# PicoBoard.net
KiCad netlist of a schematic drawn in EAGLE
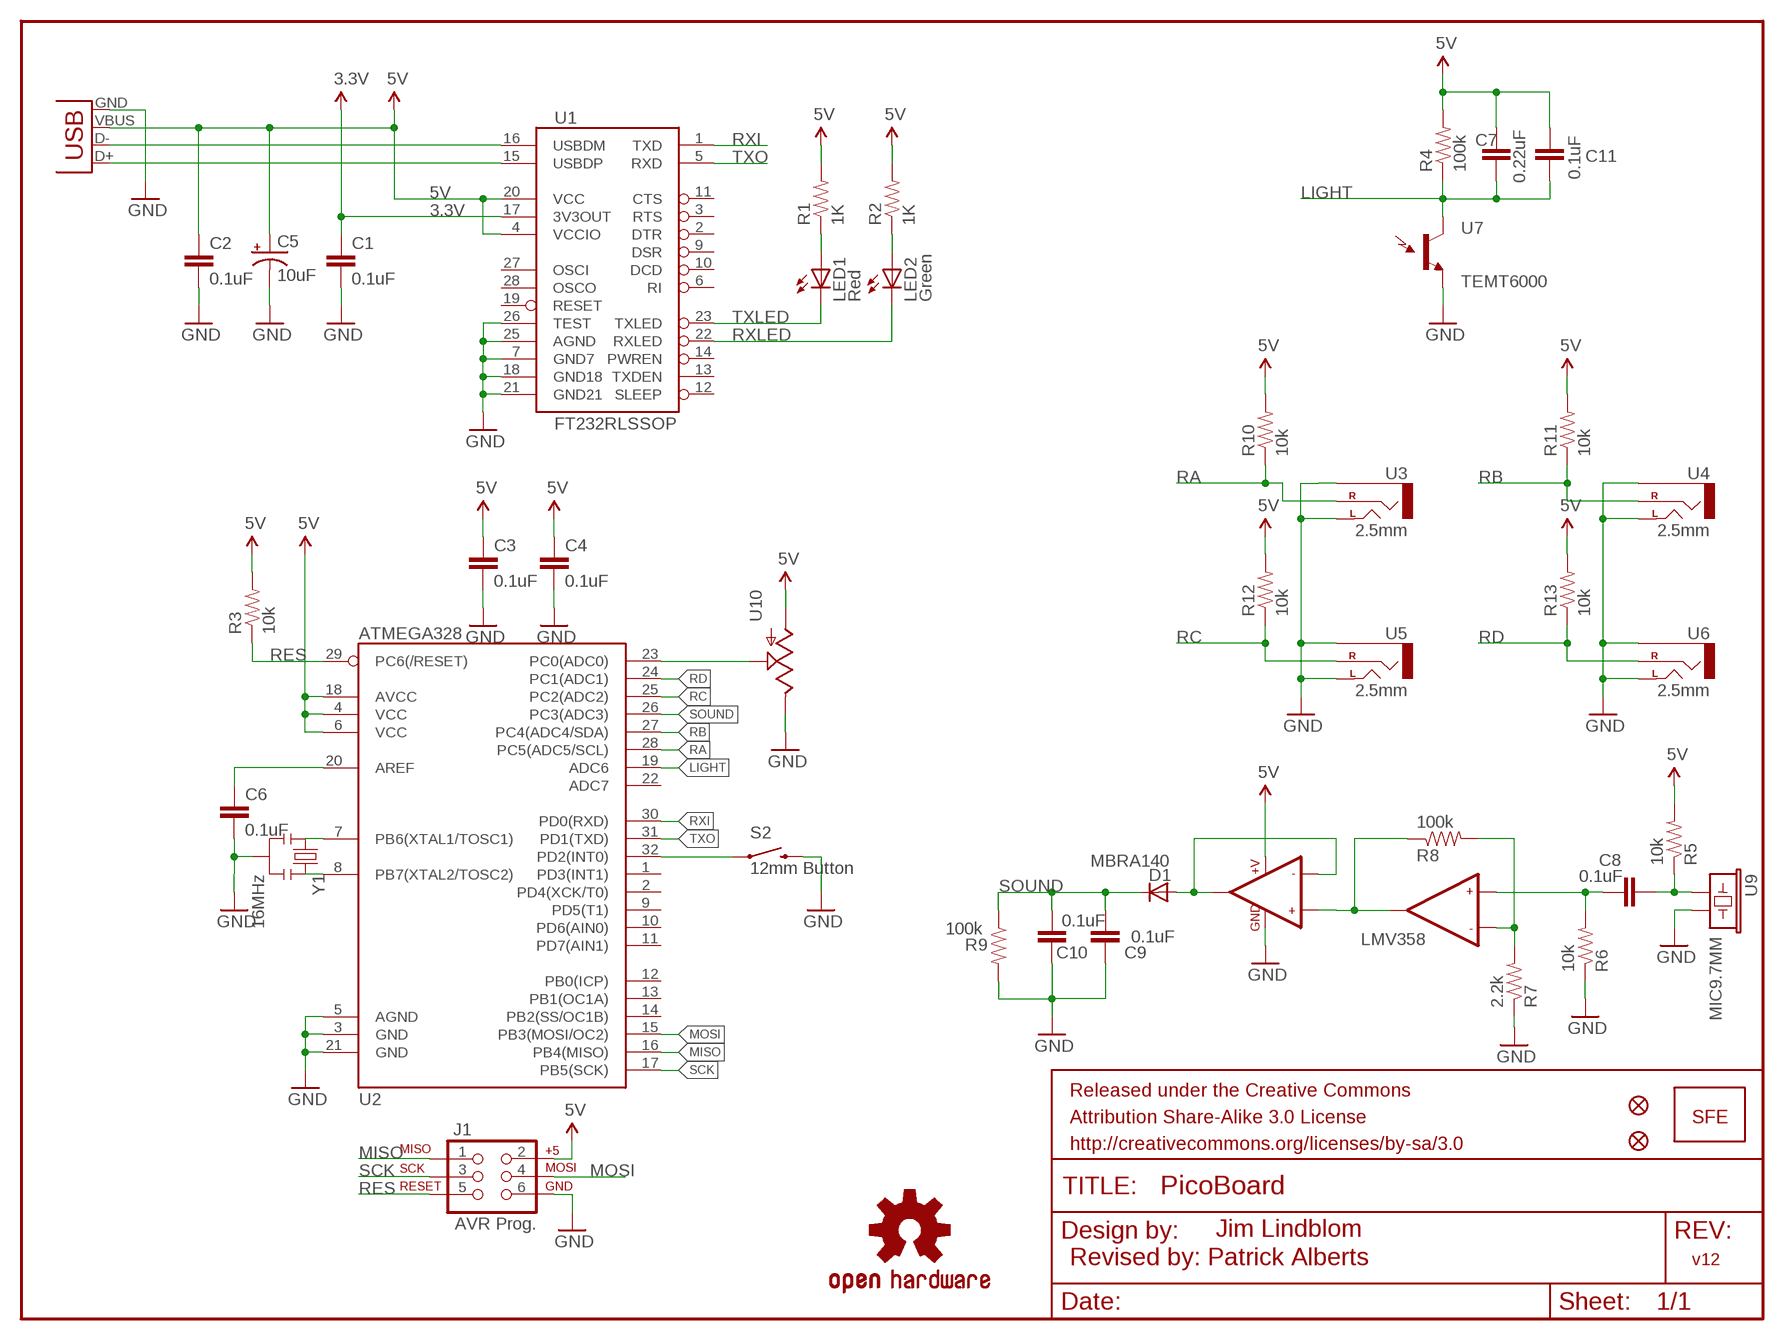
[diagram p0: schematic, sheet 1]

(export (version "E")
  (design (tool "Eeschema 10.0.6"))
  (components
    (comp (ref "C1")
      (value "0.1uF")
      (footprint "eagle-import:0603-CAP")
      (libsource (lib "eagle-import") (part "CAP0603-CAP"))
    )
    (comp (ref "C2")
      (value "0.1uF")
      (footprint "eagle-import:0603-CAP")
      (libsource (lib "eagle-import") (part "CAP0603-CAP"))
    )
    (comp (ref "C3")
      (value "0.1uF")
      (footprint "eagle-import:0603-CAP")
      (libsource (lib "eagle-import") (part "CAP0603-CAP"))
    )
    (comp (ref "C4")
      (value "0.1uF")
      (footprint "eagle-import:0603-CAP")
      (libsource (lib "eagle-import") (part "CAP0603-CAP"))
    )
    (comp (ref "C5")
      (value "10uF")
      (footprint "eagle-import:EIA3216")
      (libsource (lib "eagle-import") (part "CAP_POL1206"))
    )
    (comp (ref "C6")
      (value "0.1uF")
      (footprint "eagle-import:0603-CAP")
      (libsource (lib "eagle-import") (part "CAP0603-CAP"))
    )
    (comp (ref "C7")
      (value "0.22uF")
      (footprint "eagle-import:0603-CAP")
      (libsource (lib "eagle-import") (part "CAP0603-CAP"))
    )
    (comp (ref "C8")
      (value "0.1uF")
      (footprint "eagle-import:0603-CAP")
      (libsource (lib "eagle-import") (part "CAP0603-CAP"))
    )
    (comp (ref "C9")
      (value "0.1uF")
      (footprint "eagle-import:0603-CAP")
      (libsource (lib "eagle-import") (part "CAP0603-CAP"))
    )
    (comp (ref "C10")
      (value "0.1uF")
      (footprint "eagle-import:0603-CAP")
      (libsource (lib "eagle-import") (part "CAP0603-CAP"))
    )
    (comp (ref "C11")
      (value "0.1uF")
      (footprint "eagle-import:0603-CAP")
      (libsource (lib "eagle-import") (part "CAP0603-CAP"))
    )
    (comp (ref "D1")
      (value "MBRA140")
      (footprint "eagle-import:SMA-DIODE")
      (libsource (lib "eagle-import") (part "DIODESMA"))
    )
    (comp (ref "FID1")
      (value "FIDUCIAL1X2")
      (footprint "eagle-import:FIDUCIAL-1X2")
      (libsource (lib "eagle-import") (part "FIDUCIAL1X2"))
    )
    (comp (ref "FID2")
      (value "FIDUCIAL1X2")
      (footprint "eagle-import:FIDUCIAL-1X2")
      (libsource (lib "eagle-import") (part "FIDUCIAL1X2"))
    )
    (comp (ref "FRAME1")
      (value "FRAME-LETTER")
      (footprint "eagle-import:CREATIVE_COMMONS")
      (libsource (lib "eagle-import") (part "FRAME-LETTER"))
    )
    (comp (ref "J1")
      (value "AVR Prog.")
      (footprint "eagle-import:2X3")
      (libsource (lib "eagle-import") (part "AVR_SPI_PRG_6PTH"))
    )
    (comp (ref "JP1")
      (value "LOGO-SFENEW")
      (footprint "eagle-import:SFE-NEW-WEBLOGO")
      (libsource (lib "eagle-import") (part "LOGO-SFENEW"))
    )
    (comp (ref "LED1")
      (value "Red")
      (footprint "eagle-import:LED-0603")
      (libsource (lib "eagle-import") (part "LED0603"))
    )
    (comp (ref "LED2")
      (value "Green")
      (footprint "eagle-import:LED-0603")
      (libsource (lib "eagle-import") (part "LED0603"))
    )
    (comp (ref "LOGO1")
      (value "OSHW-LOGOL")
      (footprint "eagle-import:OSHW-LOGO-L")
      (libsource (lib "eagle-import") (part "OSHW-LOGOL"))
    )
    (comp (ref "R1")
      (value "1K")
      (footprint "eagle-import:0603-RES")
      (libsource (lib "eagle-import") (part "RESISTOR0603-RES"))
    )
    (comp (ref "R2")
      (value "1K")
      (footprint "eagle-import:0603-RES")
      (libsource (lib "eagle-import") (part "RESISTOR0603-RES"))
    )
    (comp (ref "R3")
      (value "10k")
      (footprint "eagle-import:0603-RES")
      (libsource (lib "eagle-import") (part "RESISTOR0603-RES"))
    )
    (comp (ref "R4")
      (value "100k")
      (footprint "eagle-import:0603-RES")
      (libsource (lib "eagle-import") (part "RESISTOR0603-RES"))
    )
    (comp (ref "R5")
      (value "10k")
      (footprint "eagle-import:0603-RES")
      (libsource (lib "eagle-import") (part "RESISTOR0603-RES"))
    )
    (comp (ref "R6")
      (value "10k")
      (footprint "eagle-import:0603-RES")
      (libsource (lib "eagle-import") (part "RESISTOR0603-RES"))
    )
    (comp (ref "R7")
      (value "2.2k")
      (footprint "eagle-import:0603-RES")
      (libsource (lib "eagle-import") (part "RESISTOR0603-RES"))
    )
    (comp (ref "R8")
      (value "100k")
      (footprint "eagle-import:0603-RES")
      (libsource (lib "eagle-import") (part "RESISTOR0603-RES"))
    )
    (comp (ref "R9")
      (value "100k")
      (footprint "eagle-import:0603-RES")
      (libsource (lib "eagle-import") (part "RESISTOR0603-RES"))
    )
    (comp (ref "R10")
      (value "10k")
      (footprint "eagle-import:0603-RES")
      (libsource (lib "eagle-import") (part "RESISTOR0603-RES"))
    )
    (comp (ref "R11")
      (value "10k")
      (footprint "eagle-import:0603-RES")
      (libsource (lib "eagle-import") (part "RESISTOR0603-RES"))
    )
    (comp (ref "R12")
      (value "10k")
      (footprint "eagle-import:0603-RES")
      (libsource (lib "eagle-import") (part "RESISTOR0603-RES"))
    )
    (comp (ref "R13")
      (value "10k")
      (footprint "eagle-import:0603-RES")
      (libsource (lib "eagle-import") (part "RESISTOR0603-RES"))
    )
    (comp (ref "S2")
      (value "12mm Button")
      (footprint "eagle-import:TACTILE-SMD-12MM")
      (libsource (lib "eagle-import") (part "SWITCH-MOMENTARY-2SMD-12MM"))
    )
    (comp (ref "U1")
      (value "FT232RLSSOP")
      (footprint "eagle-import:SSOP28DB")
      (libsource (lib "eagle-import") (part "FT232RLSSOP"))
    )
    (comp (ref "U2")
      (value "ATMEGA328")
      (footprint "eagle-import:TQFP32-08")
      (libsource (lib "eagle-import") (part "ATMEGA168"))
    )
    (comp (ref "U3")
      (value "2.5mm")
      (footprint "eagle-import:STEREOJACK2.5MM")
      (libsource (lib "eagle-import") (part "AUDIO-JACK1{colon}1"))
    )
    (comp (ref "U4")
      (value "2.5mm")
      (footprint "eagle-import:STEREOJACK2.5MM")
      (libsource (lib "eagle-import") (part "AUDIO-JACK1{colon}1"))
    )
    (comp (ref "U5")
      (value "2.5mm")
      (footprint "eagle-import:STEREOJACK2.5MM")
      (libsource (lib "eagle-import") (part "AUDIO-JACK1{colon}1"))
    )
    (comp (ref "U6")
      (value "2.5mm")
      (footprint "eagle-import:STEREOJACK2.5MM")
      (libsource (lib "eagle-import") (part "AUDIO-JACK1{colon}1"))
    )
    (comp (ref "U7")
      (value "TEMT6000")
      (footprint "eagle-import:TEMT6000-SEN")
      (libsource (lib "eagle-import") (part "TEMT6000"))
    )
    (comp (ref "U8")
      (value "LMV358")
      (footprint "eagle-import:SO08")
      (libsource (lib "eagle-import") (part "LMV358"))
    )
    (comp (ref "U9")
      (value "MIC9.7MM")
      (footprint "eagle-import:MIC-9.7MM")
      (libsource (lib "eagle-import") (part "MIC9.7MM"))
    )
    (comp (ref "U10")
      (value "SLIDER60MM")
      (footprint "eagle-import:SLIDER")
      (libsource (lib "eagle-import") (part "SLIDER60MM"))
    )
    (comp (ref "X1")
      (value "USBSMD")
      (footprint "eagle-import:USB-MINIB")
      (libsource (lib "eagle-import") (part "USBSMD"))
    )
    (comp (ref "Y1")
      (value "16MHz")
      (footprint "eagle-import:RESONATOR-SMD")
      (libsource (lib "eagle-import") (part "RESONATORSMD"))
    )
  )
  (nets
    (net (code "1") (name "/RES") (class "Default")
      (node (ref "J1") (pin "5") (pinfunction "5_5") (pintype "passive"))
      (node (ref "R3") (pin "1") (pinfunction "1_1") (pintype "passive"))
      (node (ref "U2") (pin "29") (pinfunction "PC6(/RESET)_29") (pintype "bidirectional"))
    )
    (net (code "2") (name "/RXLED") (class "Default")
      (node (ref "LED2") (pin "C") (pinfunction "C_C") (pintype "passive"))
      (node (ref "U1") (pin "22") (pinfunction "RXLED_22") (pintype "input"))
    )
    (net (code "3") (name "/TXLED") (class "Default")
      (node (ref "LED1") (pin "C") (pinfunction "C_C") (pintype "passive"))
      (node (ref "U1") (pin "23") (pinfunction "TXLED_23") (pintype "input"))
    )
    (net (code "4") (name "3.3V") (class "Default")
      (node (ref "C1") (pin "1") (pinfunction "1_1") (pintype "passive"))
      (node (ref "U1") (pin "17") (pinfunction "3V3OUT_17") (pintype "output"))
    )
    (net (code "5") (name "5V") (class "Default")
      (node (ref "C11") (pin "1") (pinfunction "1_1") (pintype "passive"))
      (node (ref "C2") (pin "1") (pinfunction "1_1") (pintype "passive"))
      (node (ref "C3") (pin "1") (pinfunction "1_1") (pintype "passive"))
      (node (ref "C4") (pin "1") (pinfunction "1_1") (pintype "passive"))
      (node (ref "C5") (pin "A") (pinfunction "+_A") (pintype "passive"))
      (node (ref "C7") (pin "1") (pinfunction "1_1") (pintype "passive"))
      (node (ref "J1") (pin "2") (pinfunction "2_2") (pintype "passive"))
      (node (ref "R1") (pin "2") (pinfunction "2_2") (pintype "passive"))
      (node (ref "R10") (pin "2") (pinfunction "2_2") (pintype "passive"))
      (node (ref "R11") (pin "2") (pinfunction "2_2") (pintype "passive"))
      (node (ref "R12") (pin "2") (pinfunction "2_2") (pintype "passive"))
      (node (ref "R13") (pin "2") (pinfunction "2_2") (pintype "passive"))
      (node (ref "R2") (pin "2") (pinfunction "2_2") (pintype "passive"))
      (node (ref "R3") (pin "2") (pinfunction "2_2") (pintype "passive"))
      (node (ref "R4") (pin "2") (pinfunction "2_2") (pintype "passive"))
      (node (ref "R5") (pin "2") (pinfunction "2_2") (pintype "passive"))
      (node (ref "U1") (pin "20") (pinfunction "VCC_20") (pintype "power_in"))
      (node (ref "U1") (pin "4") (pinfunction "VCCIO_4") (pintype "power_in"))
      (node (ref "U10") (pin "3") (pinfunction "A_3") (pintype "passive"))
      (node (ref "U2") (pin "18") (pinfunction "AVCC_18") (pintype "bidirectional"))
      (node (ref "U2") (pin "4") (pinfunction "VCC_4") (pintype "bidirectional"))
      (node (ref "U2") (pin "6") (pinfunction "VCC_6") (pintype "bidirectional"))
      (node (ref "U8") (pin "8") (pinfunction "+V_8") (pintype "power_in"))
      (node (ref "X1") (pin "VBUS") (pinfunction "VBUS_VBUS") (pintype "bidirectional"))
    )
    (net (code "6") (name "GND") (class "Default")
      (node (ref "C1") (pin "2") (pinfunction "2_2") (pintype "passive"))
      (node (ref "C10") (pin "1") (pinfunction "1_1") (pintype "passive"))
      (node (ref "C2") (pin "2") (pinfunction "2_2") (pintype "passive"))
      (node (ref "C3") (pin "2") (pinfunction "2_2") (pintype "passive"))
      (node (ref "C4") (pin "2") (pinfunction "2_2") (pintype "passive"))
      (node (ref "C5") (pin "C") (pinfunction "-_C") (pintype "passive"))
      (node (ref "C6") (pin "2") (pinfunction "2_2") (pintype "passive"))
      (node (ref "C9") (pin "1") (pinfunction "1_1") (pintype "passive"))
      (node (ref "J1") (pin "6") (pinfunction "6_6") (pintype "passive"))
      (node (ref "R6") (pin "1") (pinfunction "1_1") (pintype "passive"))
      (node (ref "R7") (pin "1") (pinfunction "1_1") (pintype "passive"))
      (node (ref "R9") (pin "2") (pinfunction "2_2") (pintype "passive"))
      (node (ref "S2") (pin "3") (pinfunction "2_3") (pintype "passive"))
      (node (ref "U1") (pin "18") (pinfunction "GND18_18") (pintype "power_in"))
      (node (ref "U1") (pin "21") (pinfunction "GND21_21") (pintype "power_in"))
      (node (ref "U1") (pin "25") (pinfunction "AGND_25") (pintype "power_in"))
      (node (ref "U1") (pin "26") (pinfunction "TEST_26") (pintype "input"))
      (node (ref "U1") (pin "7") (pinfunction "GND7_7") (pintype "power_in"))
      (node (ref "U10") (pin "1") (pinfunction "E_1") (pintype "passive"))
      (node (ref "U2") (pin "21") (pinfunction "GND_21") (pintype "bidirectional"))
      (node (ref "U2") (pin "3") (pinfunction "GND_3") (pintype "bidirectional"))
      (node (ref "U2") (pin "5") (pinfunction "AGND_5") (pintype "bidirectional"))
      (node (ref "U3") (pin "1") (pinfunction "LEFT_1") (pintype "bidirectional"))
      (node (ref "U3") (pin "5") (pinfunction "SLEEVE_5") (pintype "bidirectional"))
      (node (ref "U4") (pin "1") (pinfunction "LEFT_1") (pintype "bidirectional"))
      (node (ref "U4") (pin "5") (pinfunction "SLEEVE_5") (pintype "bidirectional"))
      (node (ref "U5") (pin "1") (pinfunction "LEFT_1") (pintype "bidirectional"))
      (node (ref "U5") (pin "5") (pinfunction "SLEEVE_5") (pintype "bidirectional"))
      (node (ref "U6") (pin "1") (pinfunction "LEFT_1") (pintype "bidirectional"))
      (node (ref "U6") (pin "5") (pinfunction "SLEEVE_5") (pintype "bidirectional"))
      (node (ref "U7") (pin "EMITTER") (pinfunction "E1_EMITTER") (pintype "passive"))
      (node (ref "U8") (pin "4") (pinfunction "GND_4") (pintype "power_in"))
      (node (ref "U9") (pin "2") (pinfunction "2_2") (pintype "passive"))
      (node (ref "X1") (pin "GND") (pinfunction "GND_GND") (pintype "bidirectional"))
      (node (ref "Y1") (pin "2") (pinfunction "2_2") (pintype "passive"))
    )
    (net (code "7") (name "LIGHT") (class "Default")
      (node (ref "C11") (pin "2") (pinfunction "2_2") (pintype "passive"))
      (node (ref "C7") (pin "2") (pinfunction "2_2") (pintype "passive"))
      (node (ref "R4") (pin "1") (pinfunction "1_1") (pintype "passive"))
      (node (ref "U2") (pin "19") (pinfunction "ADC6_19") (pintype "bidirectional"))
      (node (ref "U7") (pin "COLLECTOR") (pinfunction "C1_COLLECTOR") (pintype "passive"))
    )
    (net (code "8") (name "MISO") (class "Default")
      (node (ref "J1") (pin "1") (pinfunction "1_1") (pintype "passive"))
      (node (ref "U2") (pin "16") (pinfunction "PB4(MISO)_16") (pintype "bidirectional"))
    )
    (net (code "9") (name "MOSI") (class "Default")
      (node (ref "J1") (pin "4") (pinfunction "4_4") (pintype "passive"))
      (node (ref "U2") (pin "15") (pinfunction "PB3(MOSI/OC2)_15") (pintype "bidirectional"))
    )
    (net (code "10") (name "Net-(C8-Pad1)") (class "Default")
      (node (ref "C8") (pin "1") (pinfunction "1_1") (pintype "passive"))
      (node (ref "R5") (pin "1") (pinfunction "1_1") (pintype "passive"))
      (node (ref "U9") (pin "1") (pinfunction "1_1") (pintype "passive"))
    )
    (net (code "11") (name "Net-(LED1-PadA)") (class "Default")
      (node (ref "LED1") (pin "A") (pinfunction "A_A") (pintype "passive"))
      (node (ref "R1") (pin "1") (pinfunction "1_1") (pintype "passive"))
    )
    (net (code "12") (name "Net-(LED2-PadA)") (class "Default")
      (node (ref "LED2") (pin "A") (pinfunction "A_A") (pintype "passive"))
      (node (ref "R2") (pin "1") (pinfunction "1_1") (pintype "passive"))
    )
    (net (code "13") (name "Net-(U1-USBDM)") (class "Default")
      (node (ref "U1") (pin "16") (pinfunction "USBDM_16") (pintype "bidirectional"))
      (node (ref "X1") (pin "D-") (pinfunction "D-_D-") (pintype "bidirectional"))
    )
    (net (code "14") (name "Net-(U1-USBDP)") (class "Default")
      (node (ref "U1") (pin "15") (pinfunction "USBDP_15") (pintype "bidirectional"))
      (node (ref "X1") (pin "D+") (pinfunction "D+_D+") (pintype "bidirectional"))
    )
    (net (code "15") (name "Net-(U2-AREF)") (class "Default")
      (node (ref "C6") (pin "1") (pinfunction "1_1") (pintype "passive"))
      (node (ref "U2") (pin "20") (pinfunction "AREF_20") (pintype "bidirectional"))
    )
    (net (code "16") (name "Net-(U2-PB6(XTAL1{slash}TOSC1))") (class "Default")
      (node (ref "U2") (pin "7") (pinfunction "PB6(XTAL1/TOSC1)_7") (pintype "bidirectional"))
      (node (ref "Y1") (pin "1") (pinfunction "1_1") (pintype "passive"))
    )
    (net (code "17") (name "Net-(U2-PB7(XTAL2{slash}TOSC2))") (class "Default")
      (node (ref "U2") (pin "8") (pinfunction "PB7(XTAL2/TOSC2)_8") (pintype "bidirectional"))
      (node (ref "Y1") (pin "3") (pinfunction "3_3") (pintype "passive"))
    )
    (net (code "18") (name "Net-(U2-PD2(INT0))") (class "Default")
      (node (ref "S2") (pin "1") (pinfunction "1_1") (pintype "passive"))
      (node (ref "U2") (pin "32") (pinfunction "PD2(INT0)_32") (pintype "bidirectional"))
    )
    (net (code "19") (name "Net-(U8A-+IN1)") (class "Default")
      (node (ref "R8") (pin "1") (pinfunction "1_1") (pintype "passive"))
      (node (ref "U8") (pin "3") (pinfunction "+IN1_3") (pintype "input"))
      (node (ref "U8") (pin "7") (pinfunction "OUT2_7") (pintype "output"))
    )
    (net (code "20") (name "Net-(U8A--IN1)") (class "Default")
      (node (ref "D1") (pin "A") (pinfunction "A_A") (pintype "passive"))
      (node (ref "U8") (pin "1") (pinfunction "OUT1_1") (pintype "output"))
      (node (ref "U8") (pin "2") (pinfunction "-IN1_2") (pintype "input"))
    )
    (net (code "21") (name "Net-(U8B-+IN2)") (class "Default")
      (node (ref "C8") (pin "2") (pinfunction "2_2") (pintype "passive"))
      (node (ref "R6") (pin "2") (pinfunction "2_2") (pintype "passive"))
      (node (ref "U8") (pin "5") (pinfunction "+IN2_5") (pintype "input"))
    )
    (net (code "22") (name "Net-(U8B--IN2)") (class "Default")
      (node (ref "R7") (pin "2") (pinfunction "2_2") (pintype "passive"))
      (node (ref "R8") (pin "2") (pinfunction "2_2") (pintype "passive"))
      (node (ref "U8") (pin "6") (pinfunction "-IN2_6") (pintype "input"))
    )
    (net (code "23") (name "Net-(U10-S)") (class "Default")
      (node (ref "U10") (pin "2A") (pinfunction "S_2A") (pintype "passive"))
      (node (ref "U2") (pin "23") (pinfunction "PC0(ADC0)_23") (pintype "bidirectional"))
    )
    (net (code "24") (name "RA") (class "Default")
      (node (ref "R10") (pin "1") (pinfunction "1_1") (pintype "passive"))
      (node (ref "U2") (pin "28") (pinfunction "PC5(ADC5/SCL)_28") (pintype "bidirectional"))
      (node (ref "U3") (pin "4") (pinfunction "RIGHT_4") (pintype "bidirectional"))
    )
    (net (code "25") (name "RB") (class "Default")
      (node (ref "R11") (pin "1") (pinfunction "1_1") (pintype "passive"))
      (node (ref "U2") (pin "27") (pinfunction "PC4(ADC4/SDA)_27") (pintype "bidirectional"))
      (node (ref "U4") (pin "4") (pinfunction "RIGHT_4") (pintype "bidirectional"))
    )
    (net (code "26") (name "RC") (class "Default")
      (node (ref "R12") (pin "1") (pinfunction "1_1") (pintype "passive"))
      (node (ref "U2") (pin "25") (pinfunction "PC2(ADC2)_25") (pintype "bidirectional"))
      (node (ref "U5") (pin "4") (pinfunction "RIGHT_4") (pintype "bidirectional"))
    )
    (net (code "27") (name "RD") (class "Default")
      (node (ref "R13") (pin "1") (pinfunction "1_1") (pintype "passive"))
      (node (ref "U2") (pin "24") (pinfunction "PC1(ADC1)_24") (pintype "bidirectional"))
      (node (ref "U6") (pin "4") (pinfunction "RIGHT_4") (pintype "bidirectional"))
    )
    (net (code "28") (name "RXI") (class "Default")
      (node (ref "U1") (pin "1") (pinfunction "TXD_1") (pintype "output"))
      (node (ref "U2") (pin "30") (pinfunction "PD0(RXD)_30") (pintype "bidirectional"))
    )
    (net (code "29") (name "SCK") (class "Default")
      (node (ref "J1") (pin "3") (pinfunction "3_3") (pintype "passive"))
      (node (ref "U2") (pin "17") (pinfunction "PB5(SCK)_17") (pintype "bidirectional"))
    )
    (net (code "30") (name "SOUND") (class "Default")
      (node (ref "C10") (pin "2") (pinfunction "2_2") (pintype "passive"))
      (node (ref "C9") (pin "2") (pinfunction "2_2") (pintype "passive"))
      (node (ref "D1") (pin "C") (pinfunction "C_C") (pintype "passive"))
      (node (ref "R9") (pin "1") (pinfunction "1_1") (pintype "passive"))
      (node (ref "U2") (pin "26") (pinfunction "PC3(ADC3)_26") (pintype "bidirectional"))
    )
    (net (code "31") (name "TXO") (class "Default")
      (node (ref "U1") (pin "5") (pinfunction "RXD_5") (pintype "input"))
      (node (ref "U2") (pin "31") (pinfunction "PD1(TXD)_31") (pintype "bidirectional"))
    )
    (net (code "32") (name "unconnected-(U1-CTS-Pad11)") (class "Default")
      (node (ref "U1") (pin "11") (pinfunction "CTS_11") (pintype "input"))
    )
    (net (code "33") (name "unconnected-(U1-DCD-Pad10)") (class "Default")
      (node (ref "U1") (pin "10") (pinfunction "DCD_10") (pintype "input"))
    )
    (net (code "34") (name "unconnected-(U1-DSR-Pad9)") (class "Default")
      (node (ref "U1") (pin "9") (pinfunction "DSR_9") (pintype "input"))
    )
    (net (code "35") (name "unconnected-(U1-DTR-Pad2)") (class "Default")
      (node (ref "U1") (pin "2") (pinfunction "DTR_2") (pintype "output"))
    )
    (net (code "36") (name "unconnected-(U1-OSCI-Pad27)") (class "Default")
      (node (ref "U1") (pin "27") (pinfunction "OSCI_27") (pintype "input"))
    )
    (net (code "37") (name "unconnected-(U1-OSCO-Pad28)") (class "Default")
      (node (ref "U1") (pin "28") (pinfunction "OSCO_28") (pintype "output"))
    )
    (net (code "38") (name "unconnected-(U1-PWREN-Pad14)") (class "Default")
      (node (ref "U1") (pin "14") (pinfunction "PWREN_14") (pintype "input"))
    )
    (net (code "39") (name "unconnected-(U1-RESET-Pad19)") (class "Default")
      (node (ref "U1") (pin "19") (pinfunction "RESET_19") (pintype "input"))
    )
    (net (code "40") (name "unconnected-(U1-RI-Pad6)") (class "Default")
      (node (ref "U1") (pin "6") (pinfunction "RI_6") (pintype "input"))
    )
    (net (code "41") (name "unconnected-(U1-RTS-Pad3)") (class "Default")
      (node (ref "U1") (pin "3") (pinfunction "RTS_3") (pintype "output"))
    )
    (net (code "42") (name "unconnected-(U1-SLEEP-Pad12)") (class "Default")
      (node (ref "U1") (pin "12") (pinfunction "SLEEP_12") (pintype "input"))
    )
    (net (code "43") (name "unconnected-(U1-TXDEN-Pad13)") (class "Default")
      (node (ref "U1") (pin "13") (pinfunction "TXDEN_13") (pintype "input"))
    )
    (net (code "44") (name "unconnected-(U2-ADC7-Pad22)") (class "Default")
      (node (ref "U2") (pin "22") (pinfunction "ADC7_22") (pintype "bidirectional"))
    )
    (net (code "45") (name "unconnected-(U2-PB0(ICP)-Pad12)") (class "Default")
      (node (ref "U2") (pin "12") (pinfunction "PB0(ICP)_12") (pintype "bidirectional"))
    )
    (net (code "46") (name "unconnected-(U2-PB1(OC1A)-Pad13)") (class "Default")
      (node (ref "U2") (pin "13") (pinfunction "PB1(OC1A)_13") (pintype "bidirectional"))
    )
    (net (code "47") (name "unconnected-(U2-PB2(SS{slash}OC1B)-Pad14)") (class "Default")
      (node (ref "U2") (pin "14") (pinfunction "PB2(SS/OC1B)_14") (pintype "bidirectional"))
    )
    (net (code "48") (name "unconnected-(U2-PD3(INT1)-Pad1)") (class "Default")
      (node (ref "U2") (pin "1") (pinfunction "PD3(INT1)_1") (pintype "bidirectional"))
    )
    (net (code "49") (name "unconnected-(U2-PD4(XCK{slash}T0)-Pad2)") (class "Default")
      (node (ref "U2") (pin "2") (pinfunction "PD4(XCK/T0)_2") (pintype "bidirectional"))
    )
    (net (code "50") (name "unconnected-(U2-PD5(T1)-Pad9)") (class "Default")
      (node (ref "U2") (pin "9") (pinfunction "PD5(T1)_9") (pintype "bidirectional"))
    )
    (net (code "51") (name "unconnected-(U2-PD6(AIN0)-Pad10)") (class "Default")
      (node (ref "U2") (pin "10") (pinfunction "PD6(AIN0)_10") (pintype "bidirectional"))
    )
    (net (code "52") (name "unconnected-(U2-PD7(AIN1)-Pad11)") (class "Default")
      (node (ref "U2") (pin "11") (pinfunction "PD7(AIN1)_11") (pintype "bidirectional"))
    )
  )
)
